# 00-MAIN-TRAP.net
KiCad netlist of a schematic drawn in Altium Designer
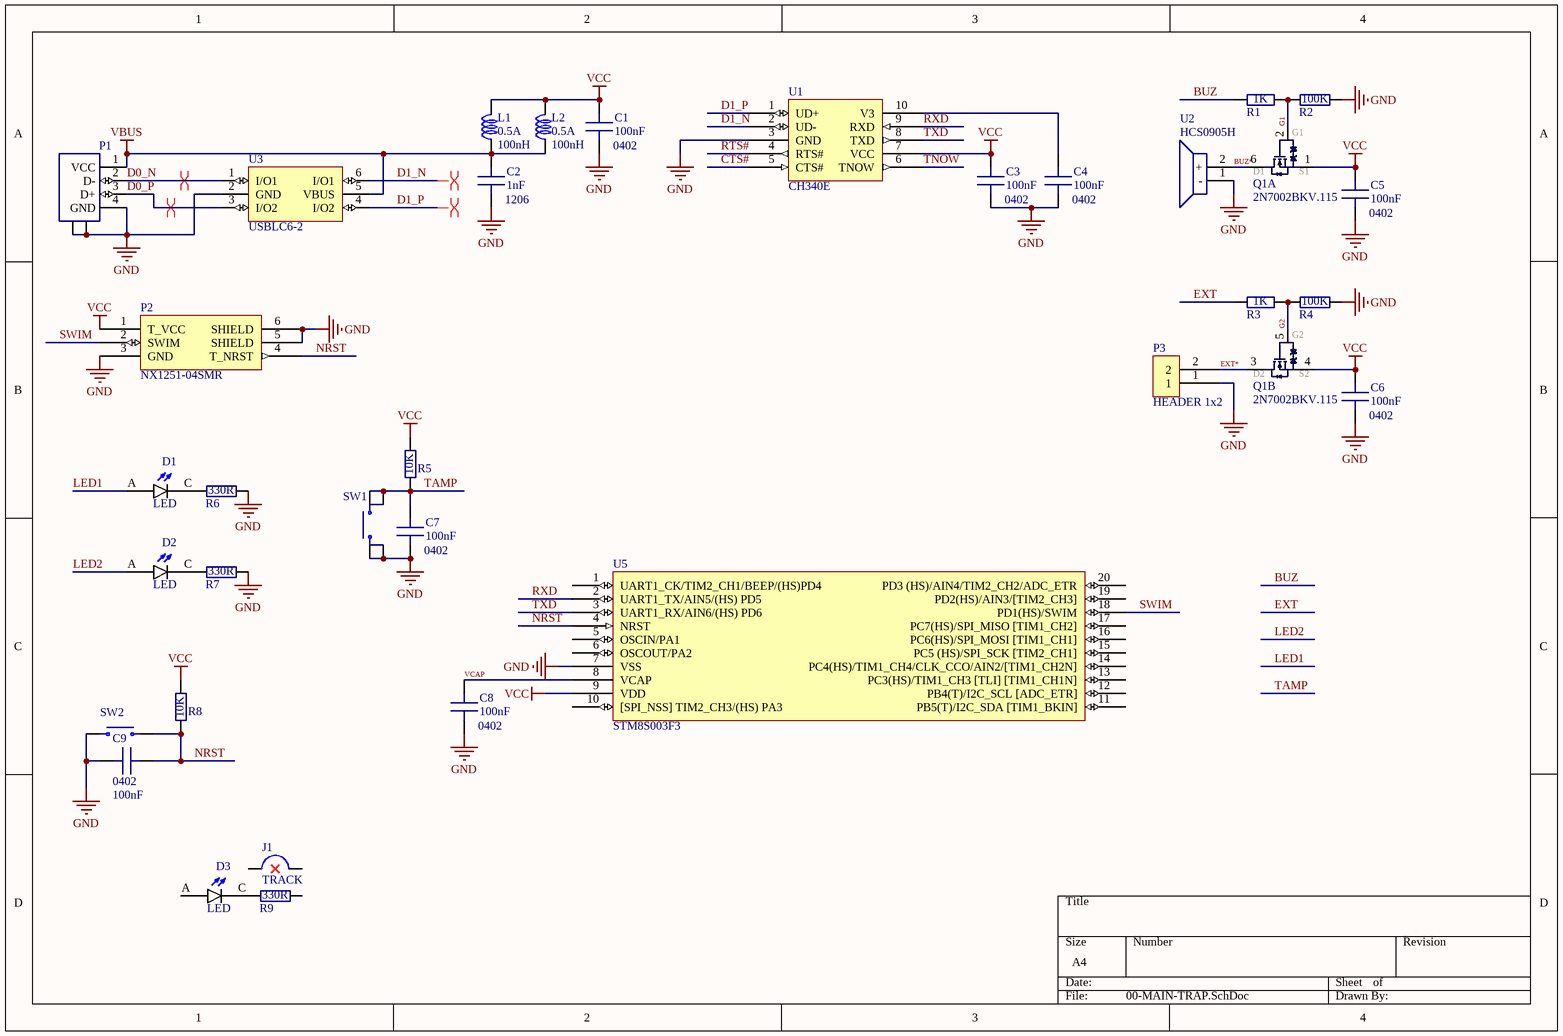
[diagram p0: 00-MAIN-TRAP.SchDoc]

(export (version "E")
  (design (tool "Eeschema 10.0.6"))
  (components
    (comp (ref "C1")
      (value "100nF")
      (footprint "C0402_NOSILK")
      (description "Ceramic capacitor")
      (fields (field (name "VOLTAGE") "16V") (field (name "SIZE") "0402"))
      (libsource (lib "A.Shelestov_Capacitors") (part "C0402_100nF_16V"))
    )
    (comp (ref "C2")
      (value "1nF")
      (footprint "C1206")
      (description "Ceramic capacitor")
      (fields (field (name "VOLTAGE") "2KV") (field (name "SIZE") "1206"))
      (libsource (lib "A.Shelestov_Capacitors") (part "C1206_1nF_2KV"))
    )
    (comp (ref "C3")
      (value "100nF")
      (footprint "C0402_NOSILK")
      (description "Ceramic capacitor")
      (fields (field (name "VOLTAGE") "16V") (field (name "SIZE") "0402"))
      (libsource (lib "A.Shelestov_Capacitors") (part "C0402_100nF_16V"))
    )
    (comp (ref "C4")
      (value "100nF")
      (footprint "C0402_NOSILK")
      (description "Ceramic capacitor")
      (fields (field (name "VOLTAGE") "16V") (field (name "SIZE") "0402"))
      (libsource (lib "A.Shelestov_Capacitors") (part "C0402_100nF_16V"))
    )
    (comp (ref "C5")
      (value "100nF")
      (footprint "C0402_NOSILK")
      (description "Ceramic capacitor")
      (fields (field (name "VOLTAGE") "16V") (field (name "SIZE") "0402"))
      (libsource (lib "A.Shelestov_Capacitors") (part "C0402_100nF_16V"))
    )
    (comp (ref "C6")
      (value "100nF")
      (footprint "C0402_NOSILK")
      (description "Ceramic capacitor")
      (fields (field (name "VOLTAGE") "16V") (field (name "SIZE") "0402"))
      (libsource (lib "A.Shelestov_Capacitors") (part "C0402_100nF_16V"))
    )
    (comp (ref "C7")
      (value "100nF")
      (footprint "C0402_NOSILK")
      (description "Ceramic capacitor")
      (fields (field (name "VOLTAGE") "16V") (field (name "SIZE") "0402"))
      (libsource (lib "A.Shelestov_Capacitors") (part "C0402_100nF_16V"))
    )
    (comp (ref "C8")
      (value "100nF")
      (footprint "C0402_NOSILK")
      (description "Ceramic capacitor")
      (fields (field (name "VOLTAGE") "16V") (field (name "SIZE") "0402"))
      (libsource (lib "A.Shelestov_Capacitors") (part "C0402_100nF_16V"))
    )
    (comp (ref "C9")
      (value "100nF")
      (footprint "C0402_NOSILK")
      (description "Ceramic capacitor")
      (fields (field (name "VOLTAGE") "16V") (field (name "SIZE") "0402"))
      (libsource (lib "A.Shelestov_Capacitors") (part "C0402_100nF_16V"))
    )
    (comp (ref "D1")
      (value "LED")
      (footprint "LED_0805_INVERTED")
      (description "Led General")
      (fields (field (name "MF") "Dialight") (field (name "MP") "598-8140-107F"))
      (libsource (lib "ComponentsLib") (part "LED"))
    )
    (comp (ref "D2")
      (value "LED")
      (footprint "LED_0805_INVERTED")
      (description "Led General")
      (fields (field (name "MF") "Dialight") (field (name "MP") "598-8140-107F"))
      (libsource (lib "ComponentsLib") (part "LED"))
    )
    (comp (ref "D3")
      (value "LED")
      (footprint "LED_0805_INVERTED")
      (description "Led General")
      (fields (field (name "MF") "Dialight") (field (name "MP") "598-8140-107F"))
      (libsource (lib "ComponentsLib") (part "LED"))
    )
    (comp (ref "J1")
      (value "TRACK")
      (footprint "TRACK-2x0.5MM")
      (description "An exposed track to cut/solder")
      (libsource (lib "ComponentsLib") (part "TRACK"))
    )
    (comp (ref "L1")
      (value "*")
      (footprint "L0603")
      (description "Inductor Generic")
      (fields (field (name "CURRENT") "0.5A") (field (name "INDUCTIVITY") "100nH"))
      (libsource (lib "A.Shelestov_Inductors") (part "L_0603_100nH_0.5A"))
    )
    (comp (ref "L2")
      (value "*")
      (footprint "L0603")
      (description "Inductor Generic")
      (fields (field (name "CURRENT") "0.5A") (field (name "INDUCTIVITY") "100nH"))
      (libsource (lib "A.Shelestov_Inductors") (part "L_0603_100nH_0.5A"))
    )
    (comp (ref "P1")
      (value "440247-2")
      (footprint "USB A type r/a male SMT")
      (description "Mini/Micro USB B Type RCPT")
      (libsource (lib "ComponentsLib") (part "CON-USB-A"))
    )
    (comp (ref "P2")
      (value "NX1251-04SMR")
      (footprint "NX1251-04SMR")
      (libsource (lib "ComponentsLib") (part "NX1251-04SMR"))
    )
    (comp (ref "P3")
      (value "HEADER 1x2")
      (footprint "HEADER 1x2 2.54")
      (libsource (lib "ComponentsLib") (part "HEADER 1x2"))
    )
    (comp (ref "Q1")
      (value "2N7002BKV.115")
      (footprint "SOT-666")
      (description "60 V, 340 mA dual N-channel Trench MOSFET")
      (libsource (lib "ComponentsLib") (part "2N7002BKV.115"))
    )
    (comp (ref "R1")
      (value "~")
      (footprint "R0402_NOSILK")
      (description "Resistor General")
      (fields (field (name "TOLERANCE") "5%") (field (name "RESISTANCE") "1K"))
      (libsource (lib "A.Shelestov_Resistors") (part "R0402_1K"))
    )
    (comp (ref "R2")
      (value "~")
      (footprint "R0402_NOSILK")
      (description "Resistor General")
      (fields (field (name "TOLERANCE") "5%") (field (name "RESISTANCE") "100K"))
      (libsource (lib "A.Shelestov_Resistors") (part "R0402_100K"))
    )
    (comp (ref "R3")
      (value "~")
      (footprint "R0402_NOSILK")
      (description "Resistor General")
      (fields (field (name "TOLERANCE") "5%") (field (name "RESISTANCE") "1K"))
      (libsource (lib "A.Shelestov_Resistors") (part "R0402_1K"))
    )
    (comp (ref "R4")
      (value "~")
      (footprint "R0402_NOSILK")
      (description "Resistor General")
      (fields (field (name "TOLERANCE") "5%") (field (name "RESISTANCE") "100K"))
      (libsource (lib "A.Shelestov_Resistors") (part "R0402_100K"))
    )
    (comp (ref "R5")
      (value "~")
      (footprint "R0402_NOSILK")
      (description "Resistor General")
      (fields (field (name "TOLERANCE") "5%") (field (name "RESISTANCE") "10K"))
      (libsource (lib "A.Shelestov_Resistors") (part "R0402_10K"))
    )
    (comp (ref "R6")
      (value "~")
      (footprint "R0402_NOSILK")
      (description "Resistor General")
      (fields (field (name "TOLERANCE") "5%") (field (name "RESISTANCE") "330R"))
      (libsource (lib "A.Shelestov_Resistors") (part "R0402_330R"))
    )
    (comp (ref "R7")
      (value "~")
      (footprint "R0402_NOSILK")
      (description "Resistor General")
      (fields (field (name "TOLERANCE") "5%") (field (name "RESISTANCE") "330R"))
      (libsource (lib "A.Shelestov_Resistors") (part "R0402_330R"))
    )
    (comp (ref "R8")
      (value "~")
      (footprint "R0402_NOSILK")
      (description "Resistor General")
      (fields (field (name "TOLERANCE") "5%") (field (name "RESISTANCE") "10K"))
      (libsource (lib "A.Shelestov_Resistors") (part "R0402_10K"))
    )
    (comp (ref "R9")
      (value "~")
      (footprint "R0402_NOSILK")
      (description "Resistor General")
      (fields (field (name "TOLERANCE") "5%") (field (name "RESISTANCE") "330R"))
      (libsource (lib "A.Shelestov_Resistors") (part "R0402_330R"))
    )
    (comp (ref "SW1")
      (value "SWITCH_GEN_4P")
      (footprint "SW_4x4x1.5")
      (description "SWITCH DIP 4.3 mm")
      (libsource (lib "ComponentsLib") (part "SWITCH_GEN_4P"))
    )
    (comp (ref "SW2")
      (value "SWITCH_GEN_2P")
      (footprint "SW_3x4x2")
      (description "SWITCH DIP 4.3 mm")
      (libsource (lib "ComponentsLib") (part "SWITCH_GEN_2P"))
    )
    (comp (ref "U1") (value "CH340E") (footprint "MSOP-10") (libsource (lib "ComponentsLib") (part "CH340E")))
    (comp (ref "U2")
      (value "HCS0905H")
      (footprint "HCS09H")
      (description "5V Buzzer GEN")
      (libsource (lib "ComponentsLib") (part "HCS0905H"))
    )
    (comp (ref "U3")
      (value "USBLC6-2")
      (footprint "SOT-666")
      (description "Very low capacitance ESD protection")
      (libsource (lib "ComponentsLib") (part "USBLC6-2"))
    )
    (comp (ref "U5")
      (value "STM8S003F3")
      (footprint "TSSOP20-6.5x4.4-0.65p")
      (description "Cheap 8bit MCU")
      (libsource (lib "ComponentsLib") (part "STM8S003F3"))
    )
  )
  (nets
    (net (code "1") (name "/BUZ") (class "Default")
      (node (ref "R1") (pin "1") (pinfunction "1_1") (pintype "passive"))
    )
    (net (code "2") (name "/BUZ*") (class "Default")
      (node (ref "Q1") (pin "6") (pinfunction "D1_6") (pintype "passive"))
      (node (ref "U2") (pin "2") (pinfunction "+_2") (pintype "passive"))
    )
    (net (code "3") (name "/CTS#") (class "Default")
      (node (ref "U1") (pin "5") (pinfunction "CTS#_5") (pintype "input"))
    )
    (net (code "4") (name "/D0_N") (class "Default")
      (node (ref "P1") (pin "2") (pinfunction "D-_2") (pintype "bidirectional"))
      (node (ref "U3") (pin "1") (pinfunction "I/O1_1") (pintype "bidirectional"))
    )
    (net (code "5") (name "/D0_P") (class "Default")
      (node (ref "P1") (pin "3") (pinfunction "D+_3") (pintype "bidirectional"))
      (node (ref "U3") (pin "3") (pinfunction "I/O2_3") (pintype "bidirectional"))
    )
    (net (code "6") (name "/D1_N") (class "Default")
      (node (ref "U1") (pin "2") (pinfunction "UD-_2") (pintype "bidirectional"))
      (node (ref "U3") (pin "6") (pinfunction "I/O1_6") (pintype "bidirectional"))
    )
    (net (code "7") (name "/D1_P") (class "Default")
      (node (ref "U1") (pin "1") (pinfunction "UD+_1") (pintype "bidirectional"))
      (node (ref "U3") (pin "4") (pinfunction "I/O2_4") (pintype "bidirectional"))
    )
    (net (code "8") (name "/EXT") (class "Default")
      (node (ref "R3") (pin "1") (pinfunction "1_1") (pintype "passive"))
    )
    (net (code "9") (name "/EXT*") (class "Default")
      (node (ref "P3") (pin "2") (pinfunction "2_2") (pintype "passive"))
      (node (ref "Q1") (pin "3") (pinfunction "D2_3") (pintype "passive"))
    )
    (net (code "10") (name "/G1") (class "Default")
      (node (ref "Q1") (pin "2") (pinfunction "G1_2") (pintype "passive"))
      (node (ref "R1") (pin "2") (pinfunction "2_2") (pintype "passive"))
      (node (ref "R2") (pin "1") (pinfunction "1_1") (pintype "passive"))
    )
    (net (code "11") (name "/G2") (class "Default")
      (node (ref "Q1") (pin "5") (pinfunction "G2_5") (pintype "passive"))
      (node (ref "R3") (pin "2") (pinfunction "2_2") (pintype "passive"))
      (node (ref "R4") (pin "1") (pinfunction "1_1") (pintype "passive"))
    )
    (net (code "12") (name "/LED1") (class "Default")
      (node (ref "D1") (pin "A") (pinfunction "A_A") (pintype "passive"))
    )
    (net (code "13") (name "/LED2") (class "Default")
      (node (ref "D2") (pin "A") (pinfunction "A_A") (pintype "passive"))
    )
    (net (code "14") (name "/NRST") (class "Default")
      (node (ref "C9") (pin "1") (pinfunction "1_1") (pintype "passive"))
      (node (ref "P2") (pin "4") (pinfunction "T_NRST_4") (pintype "output"))
      (node (ref "R8") (pin "1") (pinfunction "1_1") (pintype "passive"))
      (node (ref "SW2") (pin "2") (pinfunction "2_2") (pintype "passive"))
      (node (ref "U5") (pin "4") (pinfunction "NRST_4") (pintype "input"))
    )
    (net (code "15") (name "/RTS#") (class "Default")
      (node (ref "U1") (pin "4") (pinfunction "RTS#_4") (pintype "output"))
    )
    (net (code "16") (name "/RXD") (class "Default")
      (node (ref "U1") (pin "9") (pinfunction "RXD_9") (pintype "input"))
      (node (ref "U5") (pin "2") (pinfunction "UART1_TX/AIN5/(HS)_PD5_2") (pintype "bidirectional"))
    )
    (net (code "17") (name "/SWIM") (class "Default")
      (node (ref "P2") (pin "2") (pinfunction "SWIM_2") (pintype "bidirectional"))
      (node (ref "U5") (pin "18") (pinfunction "PD1(HS)/SWIM_18") (pintype "bidirectional"))
    )
    (net (code "18") (name "/TAMP") (class "Default")
      (node (ref "C7") (pin "2") (pinfunction "2_2") (pintype "passive"))
      (node (ref "R5") (pin "1") (pinfunction "1_1") (pintype "passive"))
      (node (ref "SW1") (pin "2") (pinfunction "2_2") (pintype "passive"))
      (node (ref "SW1") (pin "4") (pinfunction "4_4") (pintype "passive"))
    )
    (net (code "19") (name "/TNOW") (class "Default")
      (node (ref "U1") (pin "6") (pinfunction "TNOW_6") (pintype "output"))
    )
    (net (code "20") (name "/TXD") (class "Default")
      (node (ref "U1") (pin "8") (pinfunction "TXD_8") (pintype "output"))
      (node (ref "U5") (pin "3") (pinfunction "UART1_RX/AIN6/(HS)_PD6_3") (pintype "bidirectional"))
    )
    (net (code "21") (name "/VCAP") (class "Default")
      (node (ref "C8") (pin "2") (pinfunction "2_2") (pintype "passive"))
      (node (ref "U5") (pin "8") (pinfunction "VCAP_8") (pintype "power_in"))
    )
    (net (code "22") (name "GND") (class "Default")
      (node (ref "C1") (pin "1") (pinfunction "1_1") (pintype "passive"))
      (node (ref "C2") (pin "1") (pinfunction "1_1") (pintype "passive"))
      (node (ref "C3") (pin "1") (pinfunction "1_1") (pintype "passive"))
      (node (ref "C4") (pin "1") (pinfunction "1_1") (pintype "passive"))
      (node (ref "C5") (pin "1") (pinfunction "1_1") (pintype "passive"))
      (node (ref "C6") (pin "1") (pinfunction "1_1") (pintype "passive"))
      (node (ref "C7") (pin "1") (pinfunction "1_1") (pintype "passive"))
      (node (ref "C8") (pin "1") (pinfunction "1_1") (pintype "passive"))
      (node (ref "C9") (pin "2") (pinfunction "2_2") (pintype "passive"))
      (node (ref "P1") (pin "4") (pinfunction "GND_4") (pintype "passive"))
      (node (ref "P1") (pin "SHIELD") (pinfunction "SHIELD_SHIELD") (pintype "power_in"))
      (node (ref "P2") (pin "3") (pinfunction "GND_3") (pintype "passive"))
      (node (ref "P2") (pin "5") (pinfunction "SHIELD_5") (pintype "passive"))
      (node (ref "P2") (pin "6") (pinfunction "SHIELD_6") (pintype "passive"))
      (node (ref "P3") (pin "1") (pinfunction "1_1") (pintype "passive"))
      (node (ref "R2") (pin "2") (pinfunction "2_2") (pintype "passive"))
      (node (ref "R4") (pin "2") (pinfunction "2_2") (pintype "passive"))
      (node (ref "R6") (pin "2") (pinfunction "2_2") (pintype "passive"))
      (node (ref "R7") (pin "2") (pinfunction "2_2") (pintype "passive"))
      (node (ref "SW1") (pin "1") (pinfunction "1_1") (pintype "passive"))
      (node (ref "SW1") (pin "3") (pinfunction "3_3") (pintype "passive"))
      (node (ref "SW2") (pin "1") (pinfunction "1_1") (pintype "passive"))
      (node (ref "U1") (pin "3") (pinfunction "GND_3") (pintype "power_in"))
      (node (ref "U2") (pin "1") (pinfunction "-_1") (pintype "passive"))
      (node (ref "U3") (pin "2") (pinfunction "GND_2") (pintype "power_in"))
      (node (ref "U5") (pin "7") (pinfunction "VSS_7") (pintype "power_in"))
    )
    (net (code "23") (name "Net-(D1-PadC)") (class "Default")
      (node (ref "D1") (pin "C") (pinfunction "C_C") (pintype "passive"))
      (node (ref "R6") (pin "1") (pinfunction "1_1") (pintype "passive"))
    )
    (net (code "24") (name "Net-(D2-PadC)") (class "Default")
      (node (ref "D2") (pin "C") (pinfunction "C_C") (pintype "passive"))
      (node (ref "R7") (pin "1") (pinfunction "1_1") (pintype "passive"))
    )
    (net (code "25") (name "Net-(D3-PadC)") (class "Default")
      (node (ref "D3") (pin "C") (pinfunction "C_C") (pintype "passive"))
      (node (ref "R9") (pin "1") (pinfunction "1_1") (pintype "passive"))
    )
    (net (code "26") (name "Net-(U1-V3)") (class "Default")
      (node (ref "C4") (pin "2") (pinfunction "2_2") (pintype "passive"))
      (node (ref "U1") (pin "10") (pinfunction "V3_10") (pintype "power_in"))
    )
    (net (code "27") (name "VBUS") (class "Default")
      (node (ref "C2") (pin "2") (pinfunction "2_2") (pintype "passive"))
      (node (ref "L1") (pin "1") (pinfunction "1_1") (pintype "passive"))
      (node (ref "L2") (pin "1") (pinfunction "1_1") (pintype "passive"))
      (node (ref "P1") (pin "1") (pinfunction "VCC_1") (pintype "power_in"))
      (node (ref "U3") (pin "5") (pinfunction "VBUS_5") (pintype "power_in"))
    )
    (net (code "28") (name "VCC") (class "Default")
      (node (ref "C1") (pin "2") (pinfunction "2_2") (pintype "passive"))
      (node (ref "C3") (pin "2") (pinfunction "2_2") (pintype "passive"))
      (node (ref "C5") (pin "2") (pinfunction "2_2") (pintype "passive"))
      (node (ref "C6") (pin "2") (pinfunction "2_2") (pintype "passive"))
      (node (ref "L1") (pin "2") (pinfunction "2_2") (pintype "passive"))
      (node (ref "L2") (pin "2") (pinfunction "2_2") (pintype "passive"))
      (node (ref "P2") (pin "1") (pinfunction "T_VCC_1") (pintype "power_in"))
      (node (ref "Q1") (pin "1") (pinfunction "S1_1") (pintype "passive"))
      (node (ref "Q1") (pin "4") (pinfunction "S2_4") (pintype "passive"))
      (node (ref "R5") (pin "2") (pinfunction "2_2") (pintype "passive"))
      (node (ref "R8") (pin "2") (pinfunction "2_2") (pintype "passive"))
      (node (ref "U1") (pin "7") (pinfunction "VCC_7") (pintype "power_in"))
      (node (ref "U5") (pin "9") (pinfunction "VDD_9") (pintype "power_in"))
    )
    (net (code "29") (name "unconnected-(D3-PadA)") (class "Default")
      (node (ref "D3") (pin "A") (pinfunction "A_A") (pintype "passive"))
    )
    (net (code "30") (name "unconnected-(J1-Pad1)") (class "Default")
      (node (ref "J1") (pin "1") (pinfunction "1_1") (pintype "passive"))
    )
    (net (code "31") (name "unconnected-(J1-Pad2)") (class "Default")
      (node (ref "J1") (pin "2") (pinfunction "2_2") (pintype "passive"))
    )
    (net (code "32") (name "unconnected-(R9-Pad2)") (class "Default")
      (node (ref "R9") (pin "2") (pinfunction "2_2") (pintype "passive"))
    )
    (net (code "33") (name "unconnected-(U5-OSCIN{slash}PA1-Pad5)") (class "Default")
      (node (ref "U5") (pin "5") (pinfunction "OSCIN/PA1_5") (pintype "bidirectional"))
    )
    (net (code "34") (name "unconnected-(U5-OSCOUT{slash}PA2-Pad6)") (class "Default")
      (node (ref "U5") (pin "6") (pinfunction "OSCOUT/PA2_6") (pintype "bidirectional"))
    )
    (net (code "35") (name "unconnected-(U5-PB4(T){slash}I2C_SCL_[ADC_ETR]-Pad12)") (class "Default")
      (node (ref "U5") (pin "12") (pinfunction "PB4(T)/I2C_SCL_[ADC_ETR]_12") (pintype "bidirectional"))
    )
    (net (code "36") (name "unconnected-(U5-PB5(T){slash}I2C_SDA_[TIM1_BKIN]-Pad11)") (class "Default")
      (node (ref "U5") (pin "11") (pinfunction "PB5(T)/I2C_SDA_[TIM1_BKIN]_11") (pintype "bidirectional"))
    )
    (net (code "37") (name "unconnected-(U5-PC3(HS){slash}TIM1_CH3_[TLI]_[TIM1_CH1N]-Pad13)") (class "Default")
      (node (ref "U5") (pin "13") (pinfunction "PC3(HS)/TIM1_CH3_[TLI]_[TIM1_CH1N]_13") (pintype "bidirectional"))
    )
    (net (code "38") (name "unconnected-(U5-PC4(HS){slash}TIM1_CH4{slash}CLK_CCO{slash}AIN2{slash}[TIM1_CH2N]-Pad14)") (class "Default")
      (node (ref "U5") (pin "14") (pinfunction "PC4(HS)/TIM1_CH4/CLK_CCO/AIN2/[TIM1_CH2N]_14") (pintype "bidirectional"))
    )
    (net (code "39") (name "unconnected-(U5-PC5_(HS){slash}SPI_SCK_[TIM2_CH1]-Pad15)") (class "Default")
      (node (ref "U5") (pin "15") (pinfunction "PC5_(HS)/SPI_SCK_[TIM2_CH1]_15") (pintype "bidirectional"))
    )
    (net (code "40") (name "unconnected-(U5-PC6(HS){slash}SPI_MOSI_[TIM1_CH1]-Pad16)") (class "Default")
      (node (ref "U5") (pin "16") (pinfunction "PC6(HS)/SPI_MOSI_[TIM1_CH1]_16") (pintype "bidirectional"))
    )
    (net (code "41") (name "unconnected-(U5-PC7(HS){slash}SPI_MISO_[TIM1_CH2]-Pad17)") (class "Default")
      (node (ref "U5") (pin "17") (pinfunction "PC7(HS)/SPI_MISO_[TIM1_CH2]_17") (pintype "bidirectional"))
    )
    (net (code "42") (name "unconnected-(U5-PD2(HS){slash}AIN3{slash}[TIM2_CH3]-Pad19)") (class "Default")
      (node (ref "U5") (pin "19") (pinfunction "PD2(HS)/AIN3/[TIM2_CH3]_19") (pintype "bidirectional"))
    )
    (net (code "43") (name "unconnected-(U5-PD3_(HS){slash}AIN4{slash}TIM2_CH2{slash}ADC_ETR-Pad20)") (class "Default")
      (node (ref "U5") (pin "20") (pinfunction "PD3_(HS)/AIN4/TIM2_CH2/ADC_ETR_20") (pintype "bidirectional"))
    )
    (net (code "44") (name "unconnected-(U5-UART1_CK{slash}TIM2_CH1{slash}BEEP{slash}(HS)PD4-Pad1)") (class "Default")
      (node (ref "U5") (pin "1") (pinfunction "UART1_CK/TIM2_CH1/BEEP/(HS)PD4_1") (pintype "bidirectional"))
    )
    (net (code "45") (name "unconnected-(U5-[SPI_NSS]_TIM2_CH3{slash}(HS)_PA3-Pad10)") (class "Default")
      (node (ref "U5") (pin "10") (pinfunction "[SPI_NSS]_TIM2_CH3/(HS)_PA3_10") (pintype "bidirectional"))
    )
  )
)
